# Comms.net
KiCad netlist of a schematic drawn in Altium Designer
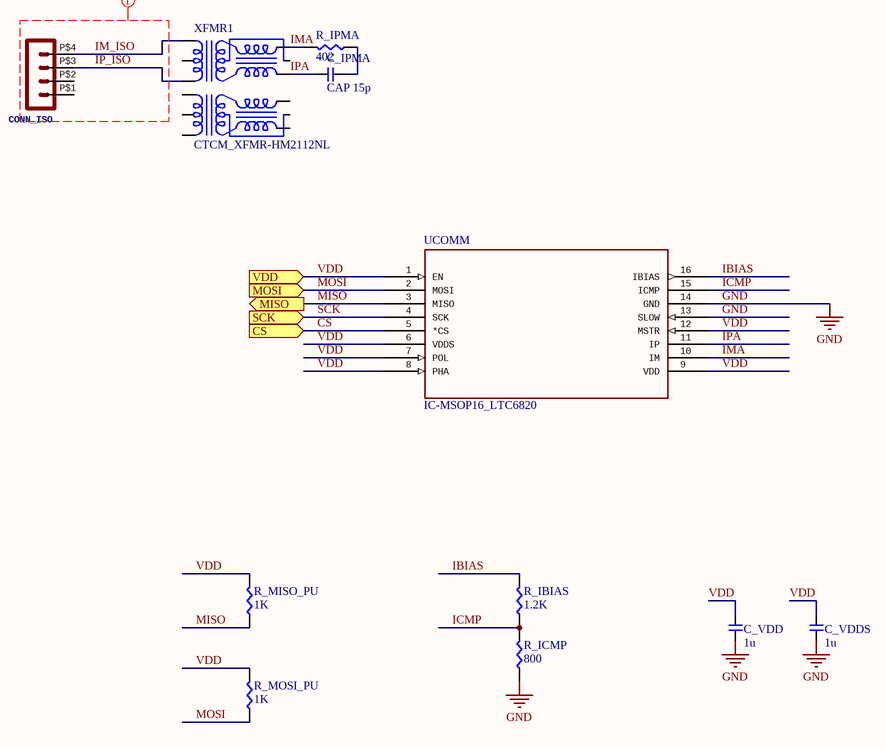
[diagram p0: Comms.SchDoc]

(export (version "E")
  (design (tool "Eeschema 10.0.6"))
  (components
    (comp (ref "CONN_ISO")
      (value "Molex - Micro-Fit 3.0 Series connector,  3.00mm (0.118\") pitch header, 4 positions.")
      (footprint "43650-0424")
      (libsource (lib "ife19_Elec_Conn_Library") (part "POS4_MF43650-0424"))
    )
    (comp (ref "C_IPMA")
      (value "CAP 15p")
      (footprint "CAP-0603")
      (description "CAP-0603")
      (libsource (lib "ife19_Elec_Library") (part "CAP-0603"))
    )
    (comp (ref "C_VDD")
      (value "1u")
      (footprint "CAP-0603")
      (libsource (lib "altium-import") (part "root_1_CAP-0603_"))
    )
    (comp (ref "C_VDDS")
      (value "1u")
      (footprint "CAP-0603")
      (libsource (lib "altium-import") (part "root_1_CAP-0603_"))
    )
    (comp (ref "R_IBIAS")
      (value "1.2K")
      (footprint "RES-0603")
      (libsource (lib "altium-import") (part "root_1_RES-0603_"))
    )
    (comp (ref "R_ICMP")
      (value "800")
      (footprint "RES-0603")
      (libsource (lib "altium-import") (part "root_1_RES-0603_"))
    )
    (comp (ref "R_IPMA")
      (value "402")
      (footprint "RES-0603")
      (libsource (lib "ife19_Elec_Library") (part "RES-0603"))
    )
    (comp (ref "R_MISO_PU")
      (value "1K")
      (footprint "RES-0603")
      (libsource (lib "altium-import") (part "root_1_RES-0603_"))
    )
    (comp (ref "R_MOSI_PU")
      (value "1K")
      (footprint "RES-0603")
      (libsource (lib "altium-import") (part "root_1_RES-0603_"))
    )
    (comp (ref "UCOMM")
      (value "IC-MSOP16_LTC6820")
      (footprint "MSOP16")
      (libsource (lib "altium-import") (part "root_0_IC-MSOP16_LTC6820_"))
    )
    (comp (ref "XFMR1")
      (value "CTCM_XFMR-HM2112NL")
      (footprint "HM2112NL")
      (libsource (lib "ife19_Elec_Library") (part "CTCM_XFMR-HM2112NL"))
    )
  )
  (nets
    (net (code "1") (name "/CS") (class "Default")
      (node (ref "UCOMM") (pin "5") (pinfunction "*CS_5") (pintype "passive"))
    )
    (net (code "2") (name "/IBIAS") (class "Default")
      (node (ref "R_IBIAS") (pin "2") (pinfunction "2_2") (pintype "passive"))
      (node (ref "UCOMM") (pin "16") (pinfunction "IBIAS_16") (pintype "output"))
    )
    (net (code "3") (name "/ICMP") (class "Default")
      (node (ref "R_IBIAS") (pin "1") (pinfunction "1_1") (pintype "passive"))
      (node (ref "R_ICMP") (pin "2") (pinfunction "2_2") (pintype "passive"))
      (node (ref "UCOMM") (pin "15") (pinfunction "ICMP_15") (pintype "passive"))
    )
    (net (code "4") (name "/IMA") (class "Default")
      (node (ref "R_IPMA") (pin "1") (pinfunction "1_1") (pintype "passive"))
      (node (ref "UCOMM") (pin "10") (pinfunction "IM_10") (pintype "passive"))
      (node (ref "XFMR1") (pin "12") (pinfunction "12_12") (pintype "passive"))
    )
    (net (code "5") (name "/IM_ISO") (class "Default")
      (node (ref "CONN_ISO") (pin "P$4") (pinfunction "4_P$4") (pintype "passive"))
      (node (ref "XFMR1") (pin "1") (pinfunction "1_1") (pintype "passive"))
    )
    (net (code "6") (name "/IPA") (class "Default")
      (node (ref "C_IPMA") (pin "1") (pinfunction "1_1") (pintype "passive"))
      (node (ref "UCOMM") (pin "11") (pinfunction "IP_11") (pintype "passive"))
      (node (ref "XFMR1") (pin "10") (pinfunction "10_10") (pintype "passive"))
    )
    (net (code "7") (name "/IP_ISO") (class "Default")
      (node (ref "CONN_ISO") (pin "P$3") (pinfunction "3_P$3") (pintype "passive"))
      (node (ref "XFMR1") (pin "3") (pinfunction "3_3") (pintype "passive"))
    )
    (net (code "8") (name "/MISO") (class "Default")
      (node (ref "R_MISO_PU") (pin "1") (pinfunction "1_1") (pintype "passive"))
      (node (ref "UCOMM") (pin "3") (pinfunction "MISO_3") (pintype "passive"))
    )
    (net (code "9") (name "/MOSI") (class "Default")
      (node (ref "R_MOSI_PU") (pin "1") (pinfunction "1_1") (pintype "passive"))
      (node (ref "UCOMM") (pin "2") (pinfunction "MOSI_2") (pintype "passive"))
    )
    (net (code "10") (name "/SCK") (class "Default")
      (node (ref "UCOMM") (pin "4") (pinfunction "SCK_4") (pintype "passive"))
    )
    (net (code "11") (name "/VDD") (class "Default")
      (node (ref "C_VDD") (pin "2") (pinfunction "2_2") (pintype "passive"))
      (node (ref "C_VDDS") (pin "2") (pinfunction "2_2") (pintype "passive"))
      (node (ref "R_MISO_PU") (pin "2") (pinfunction "2_2") (pintype "passive"))
      (node (ref "R_MOSI_PU") (pin "2") (pinfunction "2_2") (pintype "passive"))
      (node (ref "UCOMM") (pin "1") (pinfunction "EN_1") (pintype "input"))
      (node (ref "UCOMM") (pin "12") (pinfunction "MSTR_12") (pintype "input"))
      (node (ref "UCOMM") (pin "6") (pinfunction "VDDS_6") (pintype "power_in"))
      (node (ref "UCOMM") (pin "7") (pinfunction "POL_7") (pintype "input"))
      (node (ref "UCOMM") (pin "8") (pinfunction "PHA_8") (pintype "input"))
      (node (ref "UCOMM") (pin "9") (pinfunction "VDD_9") (pintype "power_in"))
    )
    (net (code "12") (name "GND") (class "Default")
      (node (ref "C_VDD") (pin "1") (pinfunction "1_1") (pintype "passive"))
      (node (ref "C_VDDS") (pin "1") (pinfunction "1_1") (pintype "passive"))
      (node (ref "R_ICMP") (pin "1") (pinfunction "1_1") (pintype "passive"))
      (node (ref "UCOMM") (pin "13") (pinfunction "SLOW_13") (pintype "input"))
      (node (ref "UCOMM") (pin "14") (pinfunction "GND_14") (pintype "power_in"))
    )
    (net (code "13") (name "Net-(C_IPMA-Pad2)") (class "Default")
      (node (ref "C_IPMA") (pin "2") (pinfunction "2_2") (pintype "passive"))
      (node (ref "R_IPMA") (pin "2") (pinfunction "2_2") (pintype "passive"))
    )
    (net (code "14") (name "unconnected-(CONN_ISO-1-PadP$1)") (class "Default")
      (node (ref "CONN_ISO") (pin "P$1") (pinfunction "1_P$1") (pintype "passive"))
    )
    (net (code "15") (name "unconnected-(CONN_ISO-2-PadP$2)") (class "Default")
      (node (ref "CONN_ISO") (pin "P$2") (pinfunction "2_P$2") (pintype "passive"))
    )
    (net (code "16") (name "unconnected-(XFMR1-Pad2)") (class "Default")
      (node (ref "XFMR1") (pin "2") (pinfunction "2_2") (pintype "passive"))
    )
    (net (code "17") (name "unconnected-(XFMR1-Pad4)") (class "Default")
      (node (ref "XFMR1") (pin "4") (pinfunction "4_4") (pintype "passive"))
    )
    (net (code "18") (name "unconnected-(XFMR1-Pad5)") (class "Default")
      (node (ref "XFMR1") (pin "5") (pinfunction "5_5") (pintype "passive"))
    )
    (net (code "19") (name "unconnected-(XFMR1-Pad6)") (class "Default")
      (node (ref "XFMR1") (pin "6") (pinfunction "6_6") (pintype "passive"))
    )
    (net (code "20") (name "unconnected-(XFMR1-Pad7)") (class "Default")
      (node (ref "XFMR1") (pin "7") (pinfunction "7_7") (pintype "passive"))
    )
    (net (code "21") (name "unconnected-(XFMR1-Pad8)") (class "Default")
      (node (ref "XFMR1") (pin "8") (pinfunction "8_8") (pintype "passive"))
    )
    (net (code "22") (name "unconnected-(XFMR1-Pad9)") (class "Default")
      (node (ref "XFMR1") (pin "9") (pinfunction "9_9") (pintype "passive"))
    )
    (net (code "23") (name "unconnected-(XFMR1-Pad11)") (class "Default")
      (node (ref "XFMR1") (pin "11") (pinfunction "11_11") (pintype "passive"))
    )
  )
)
